# Swerve_Hall_Effect_Sensor_Board.net
KiCad netlist of a schematic drawn in EAGLE
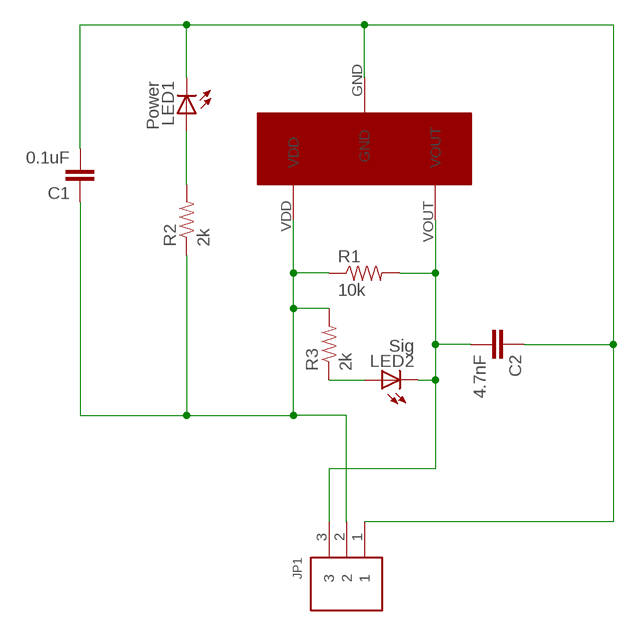
[diagram p0: schematic, sheet 1]

(export (version "E")
  (design (tool "Eeschema 10.0.6"))
  (components
    (comp (ref "C1")
      (value "0.1uF")
      (footprint "eagle-import:0603-CAP")
      (libsource (lib "eagle-import") (part "CAP0603-CAP"))
    )
    (comp (ref "C2")
      (value "4.7nF")
      (footprint "eagle-import:0603-CAP")
      (libsource (lib "eagle-import") (part "CAP0603-CAP"))
    )
    (comp (ref "JP1")
      (value "3PIN")
      (footprint "eagle-import:B3B-PH-K-S")
      (libsource (lib "eagle-import") (part "3PIN"))
    )
    (comp (ref "LED1")
      (value "Power")
      (footprint "eagle-import:LED-0603")
      (libsource (lib "eagle-import") (part "LED0603"))
    )
    (comp (ref "LED2")
      (value "Sig")
      (footprint "eagle-import:LED-0603")
      (libsource (lib "eagle-import") (part "LED0603"))
    )
    (comp (ref "R1")
      (value "10k")
      (footprint "eagle-import:0603-RES")
      (libsource (lib "eagle-import") (part "RESISTOR0603-RES"))
    )
    (comp (ref "R2")
      (value "2k")
      (footprint "eagle-import:0603-RES")
      (libsource (lib "eagle-import") (part "RESISTOR0603-RES"))
    )
    (comp (ref "R3")
      (value "2k")
      (footprint "eagle-import:0603-RES")
      (libsource (lib "eagle-import") (part "RESISTOR0603-RES"))
    )
    (comp (ref "U$1")
      (value "US5881-HALL-EFFECT")
      (footprint "eagle-import:US5881-HALL-EFFECT")
      (libsource (lib "eagle-import") (part "US5881-HALL-EFFECT"))
    )
  )
  (nets
    (net (code "1") (name "Net-(C1-Pad1)") (class "Default")
      (node (ref "C1") (pin "1") (pinfunction "1_1") (pintype "passive"))
      (node (ref "JP1") (pin "2") (pinfunction "2_2") (pintype "bidirectional"))
      (node (ref "R1") (pin "1") (pinfunction "1_1") (pintype "passive"))
      (node (ref "R2") (pin "1") (pinfunction "1_1") (pintype "passive"))
      (node (ref "R3") (pin "2") (pinfunction "2_2") (pintype "passive"))
      (node (ref "U$1") (pin "VDD") (pinfunction "VDD_VDD") (pintype "bidirectional"))
    )
    (net (code "2") (name "Net-(C1-Pad2)") (class "Default")
      (node (ref "C1") (pin "2") (pinfunction "2_2") (pintype "passive"))
      (node (ref "C2") (pin "1") (pinfunction "1_1") (pintype "passive"))
      (node (ref "JP1") (pin "1") (pinfunction "1_1") (pintype "bidirectional"))
      (node (ref "LED1") (pin "C") (pinfunction "C_C") (pintype "passive"))
      (node (ref "U$1") (pin "GND") (pinfunction "GND_GND") (pintype "bidirectional"))
    )
    (net (code "3") (name "Net-(C2-Pad2)") (class "Default")
      (node (ref "C2") (pin "2") (pinfunction "2_2") (pintype "passive"))
      (node (ref "JP1") (pin "3") (pinfunction "3_3") (pintype "bidirectional"))
      (node (ref "LED2") (pin "C") (pinfunction "C_C") (pintype "passive"))
      (node (ref "R1") (pin "2") (pinfunction "2_2") (pintype "passive"))
      (node (ref "U$1") (pin "VOUT") (pinfunction "VOUT_VOUT") (pintype "bidirectional"))
    )
    (net (code "4") (name "Net-(LED1-PadA)") (class "Default")
      (node (ref "LED1") (pin "A") (pinfunction "A_A") (pintype "passive"))
      (node (ref "R2") (pin "2") (pinfunction "2_2") (pintype "passive"))
    )
    (net (code "5") (name "Net-(LED2-PadA)") (class "Default")
      (node (ref "LED2") (pin "A") (pinfunction "A_A") (pintype "passive"))
      (node (ref "R3") (pin "1") (pinfunction "1_1") (pintype "passive"))
    )
  )
)
